# esp8266-dev-board.net
KiCad netlist of a schematic drawn in EAGLE
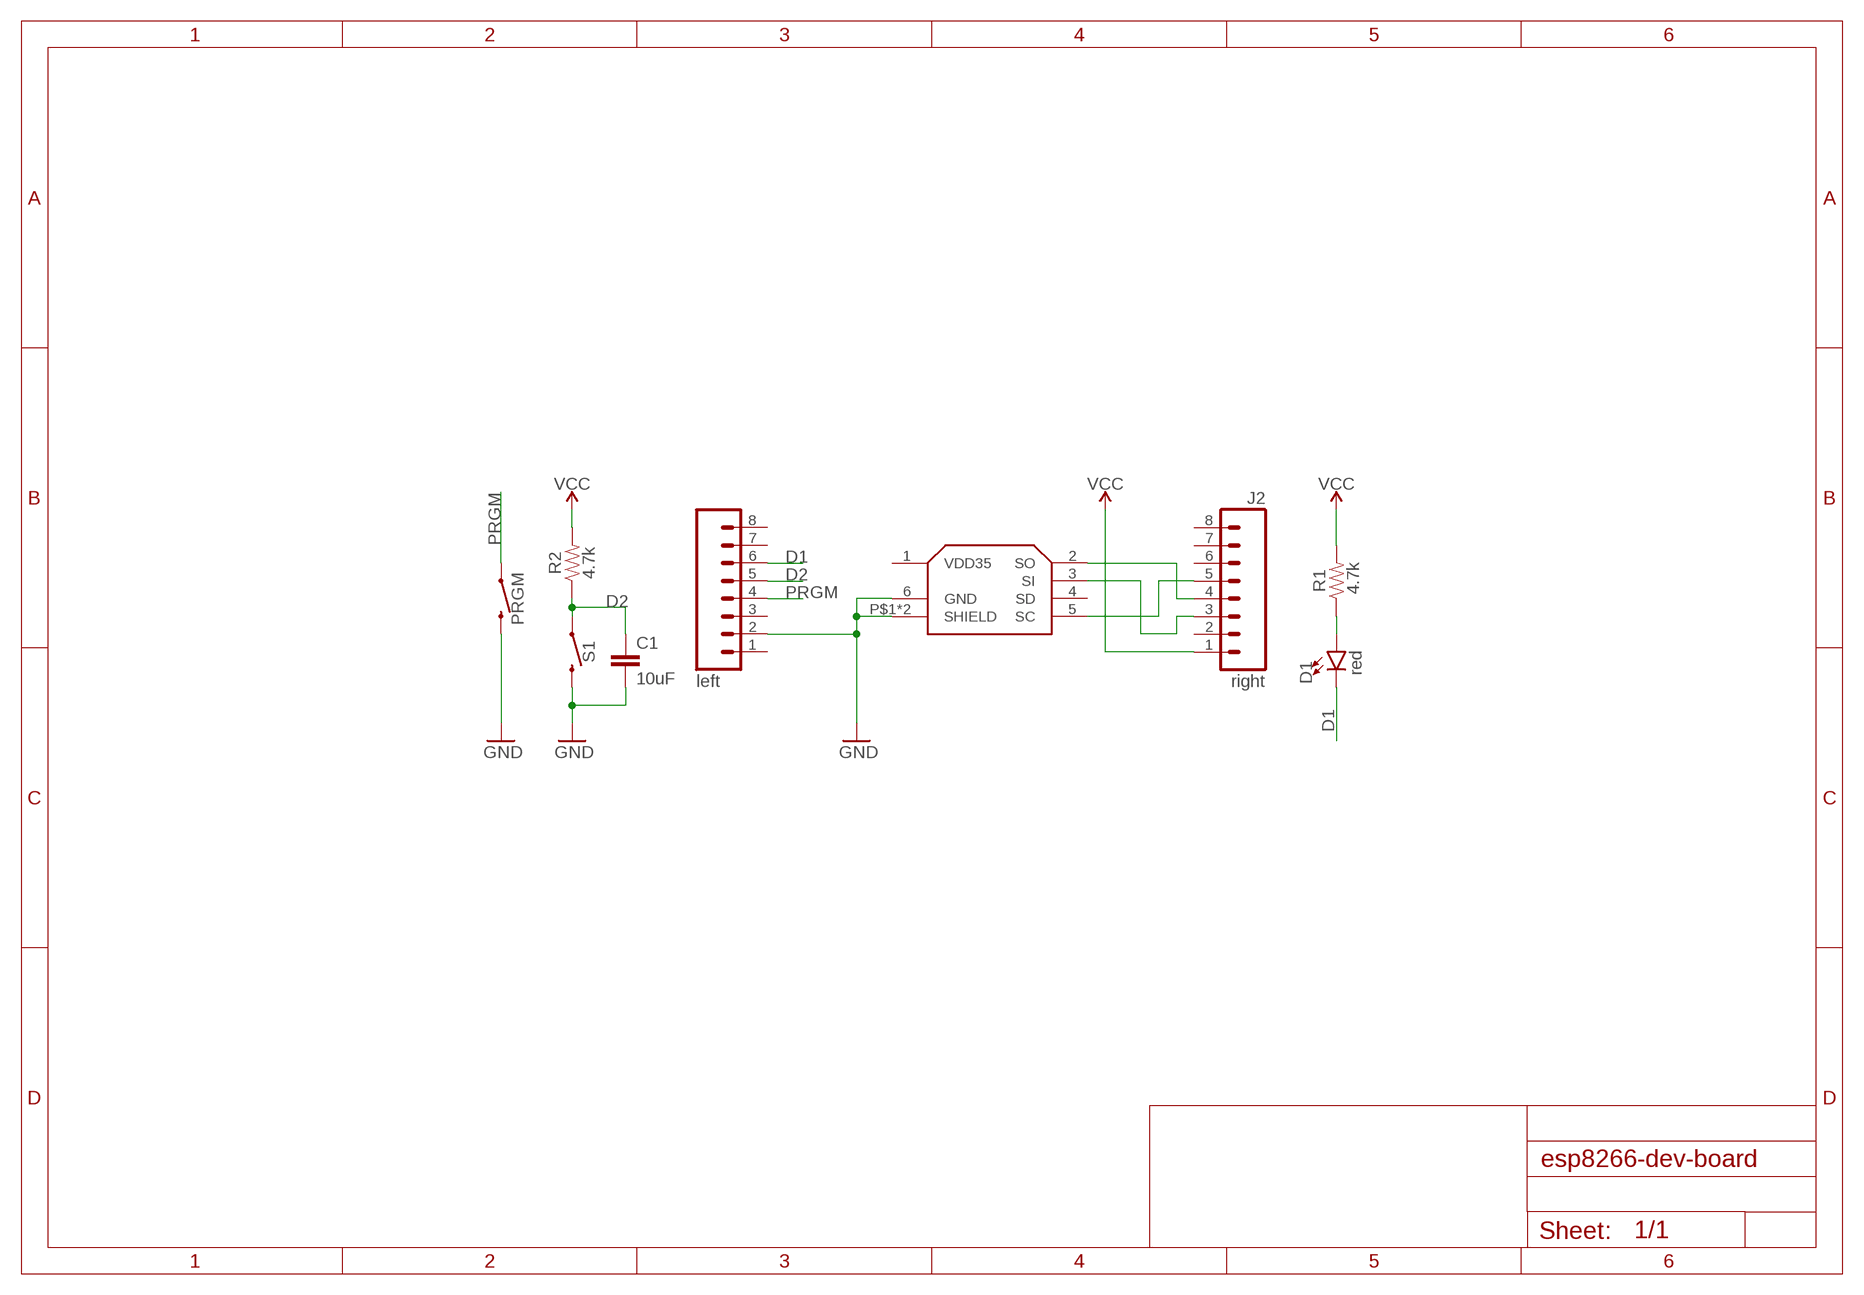
[diagram p0: schematic, sheet 1]

(export (version "E")
  (design (tool "Eeschema 10.0.6"))
  (components
    (comp (ref "C1")
      (value "10uF")
      (footprint "eagle-import:0805")
      (libsource (lib "eagle-import") (part "10UF-0805-10V-10%"))
    )
    (comp (ref "D1")
      (value "red")
      (footprint "eagle-import:LED-0603")
      (libsource (lib "eagle-import") (part "LED0603"))
    )
    (comp (ref "J1")
      (value "left")
      (footprint "eagle-import:1X08_ROUND")
      (libsource (lib "eagle-import") (part "M08"))
    )
    (comp (ref "J2")
      (value "right")
      (footprint "eagle-import:1X08_ROUND")
      (libsource (lib "eagle-import") (part "M08"))
    )
    (comp (ref "PRGM")
      (value "MOMENTARY-SWITCH-SPST-SMD-6.0X3.5MM")
      (footprint "eagle-import:TACTILE_SWITCH_SMD_6.0X3.5MM")
      (libsource (lib "eagle-import") (part "MOMENTARY-SWITCH-SPST-SMD-6.0X3.5MM"))
    )
    (comp (ref "R1")
      (value "4.7k")
      (footprint "eagle-import:0805")
      (libsource (lib "eagle-import") (part "RESISTOR0805"))
    )
    (comp (ref "R2")
      (value "4.7k")
      (footprint "eagle-import:0805")
      (libsource (lib "eagle-import") (part "RESISTOR0805"))
    )
    (comp (ref "S1")
      (value "MOMENTARY-SWITCH-SPST-SMD-6.0X3.5MM")
      (footprint "eagle-import:TACTILE_SWITCH_SMD_6.0X3.5MM")
      (libsource (lib "eagle-import") (part "MOMENTARY-SWITCH-SPST-SMD-6.0X3.5MM"))
    )
    (comp (ref "U$1")
      (value "EXT-PORT-AGB")
      (footprint "eagle-import:EXT-PORT-AGB")
      (libsource (lib "eagle-import") (part "EXT-PORT-AGB"))
    )
  )
  (nets
    (net (code "1") (name "/D1") (class "Default")
      (node (ref "D1") (pin "C") (pinfunction "C_C") (pintype "passive"))
      (node (ref "J1") (pin "6") (pinfunction "6_6") (pintype "passive"))
    )
    (net (code "2") (name "/D2") (class "Default")
      (node (ref "C1") (pin "1") (pinfunction "1_1") (pintype "passive"))
      (node (ref "J1") (pin "5") (pinfunction "5_5") (pintype "passive"))
      (node (ref "R2") (pin "1") (pinfunction "1_1") (pintype "passive"))
      (node (ref "S1") (pin "1") (pinfunction "1_1") (pintype "passive"))
    )
    (net (code "3") (name "/PRGM") (class "Default")
      (node (ref "J1") (pin "4") (pinfunction "4_4") (pintype "passive"))
      (node (ref "PRGM") (pin "1") (pinfunction "1_1") (pintype "passive"))
    )
    (net (code "4") (name "GND") (class "Default")
      (node (ref "C1") (pin "2") (pinfunction "2_2") (pintype "passive"))
      (node (ref "J1") (pin "2") (pinfunction "2_2") (pintype "passive"))
      (node (ref "PRGM") (pin "2") (pinfunction "2_2") (pintype "passive"))
      (node (ref "S1") (pin "2") (pinfunction "2_2") (pintype "passive"))
      (node (ref "U$1") (pin "6") (pinfunction "GND_6") (pintype "bidirectional"))
      (node (ref "U$1") (pin "P$1") (pinfunction "SHIELD_P$1") (pintype "bidirectional"))
      (node (ref "U$1") (pin "P$2") (pinfunction "SHIELD_P$2") (pintype "bidirectional"))
    )
    (net (code "5") (name "Net-(D1-PadA)") (class "Default")
      (node (ref "D1") (pin "A") (pinfunction "A_A") (pintype "passive"))
      (node (ref "R1") (pin "1") (pinfunction "1_1") (pintype "passive"))
    )
    (net (code "6") (name "Net-(U$1-SC)") (class "Default")
      (node (ref "J2") (pin "5") (pinfunction "5_5") (pintype "passive"))
      (node (ref "U$1") (pin "5") (pinfunction "SC_5") (pintype "bidirectional"))
    )
    (net (code "7") (name "Net-(U$1-SI)") (class "Default")
      (node (ref "J2") (pin "3") (pinfunction "3_3") (pintype "passive"))
      (node (ref "U$1") (pin "3") (pinfunction "SI_3") (pintype "bidirectional"))
    )
    (net (code "8") (name "Net-(U$1-SO)") (class "Default")
      (node (ref "J2") (pin "4") (pinfunction "4_4") (pintype "passive"))
      (node (ref "U$1") (pin "2") (pinfunction "SO_2") (pintype "bidirectional"))
    )
    (net (code "9") (name "VCC") (class "Default")
      (node (ref "J2") (pin "1") (pinfunction "1_1") (pintype "passive"))
      (node (ref "R1") (pin "2") (pinfunction "2_2") (pintype "passive"))
      (node (ref "R2") (pin "2") (pinfunction "2_2") (pintype "passive"))
    )
    (net (code "10") (name "unconnected-(J1-Pad1)") (class "Default")
      (node (ref "J1") (pin "1") (pinfunction "1_1") (pintype "passive"))
    )
    (net (code "11") (name "unconnected-(J1-Pad3)") (class "Default")
      (node (ref "J1") (pin "3") (pinfunction "3_3") (pintype "passive"))
    )
    (net (code "12") (name "unconnected-(J1-Pad7)") (class "Default")
      (node (ref "J1") (pin "7") (pinfunction "7_7") (pintype "passive"))
    )
    (net (code "13") (name "unconnected-(J1-Pad8)") (class "Default")
      (node (ref "J1") (pin "8") (pinfunction "8_8") (pintype "passive"))
    )
    (net (code "14") (name "unconnected-(J2-Pad2)") (class "Default")
      (node (ref "J2") (pin "2") (pinfunction "2_2") (pintype "passive"))
    )
    (net (code "15") (name "unconnected-(J2-Pad6)") (class "Default")
      (node (ref "J2") (pin "6") (pinfunction "6_6") (pintype "passive"))
    )
    (net (code "16") (name "unconnected-(J2-Pad7)") (class "Default")
      (node (ref "J2") (pin "7") (pinfunction "7_7") (pintype "passive"))
    )
    (net (code "17") (name "unconnected-(J2-Pad8)") (class "Default")
      (node (ref "J2") (pin "8") (pinfunction "8_8") (pintype "passive"))
    )
    (net (code "18") (name "unconnected-(U$1-SD-Pad4)") (class "Default")
      (node (ref "U$1") (pin "4") (pinfunction "SD_4") (pintype "bidirectional"))
    )
    (net (code "19") (name "unconnected-(U$1-VDD35-Pad1)") (class "Default")
      (node (ref "U$1") (pin "1") (pinfunction "VDD35_1") (pintype "bidirectional"))
    )
  )
)
